# LMD18200.net
KiCad netlist of a schematic drawn in EAGLE
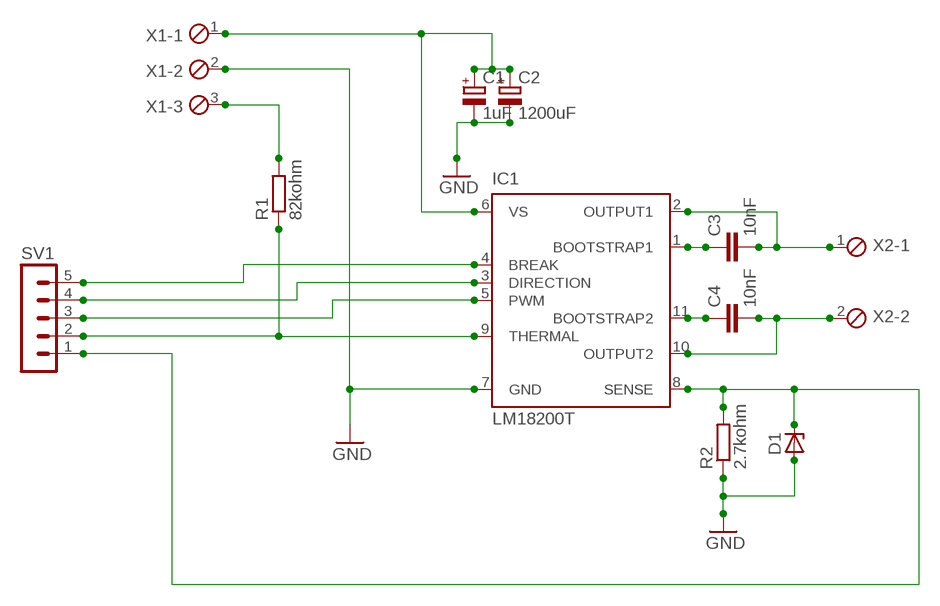
[diagram p0: schematic, sheet 1]

(export (version "E")
  (design (tool "Eeschema 10.0.6"))
  (components
    (comp (ref "C1")
      (value "1uF")
      (footprint "eagle-import:E2,5-6E")
      (libsource (lib "eagle-import") (part "CPOL-EUE2,5-6E"))
    )
    (comp (ref "C2")
      (value "1200uF")
      (footprint "eagle-import:E5-13")
      (libsource (lib "eagle-import") (part "CPOL-EUE5-13"))
    )
    (comp (ref "C3")
      (value "10nF")
      (footprint "eagle-import:C025-024X044")
      (libsource (lib "eagle-import") (part "C-EU025-024X044"))
    )
    (comp (ref "C4")
      (value "10nF")
      (footprint "eagle-import:C025-024X044")
      (libsource (lib "eagle-import") (part "C-EU025-024X044"))
    )
    (comp (ref "D1")
      (value "ZENER-DIODEZD-5")
      (footprint "eagle-import:ZDIO-5")
      (libsource (lib "eagle-import") (part "ZENER-DIODEZD-5"))
    )
    (comp (ref "IC1")
      (value "LM18200T")
      (footprint "eagle-import:TO-220-11")
      (libsource (lib "eagle-import") (part "LM18200T"))
    )
    (comp (ref "R1")
      (value "82kohm")
      (footprint "eagle-import:0204_5")
      (libsource (lib "eagle-import") (part "R-EU_0204/5"))
    )
    (comp (ref "R2")
      (value "2.7kohm")
      (footprint "eagle-import:0204_5")
      (libsource (lib "eagle-import") (part "R-EU_0204/5"))
    )
    (comp (ref "SV1")
      (value "MA05-1")
      (footprint "eagle-import:MA05-1")
      (libsource (lib "eagle-import") (part "MA05-1"))
    )
    (comp (ref "X1")
      (value "MPT3")
      (footprint "eagle-import:3POL254")
      (libsource (lib "eagle-import") (part "MPT3"))
    )
    (comp (ref "X2")
      (value "MPT2")
      (footprint "eagle-import:2POL254")
      (libsource (lib "eagle-import") (part "MPT2"))
    )
  )
  (nets
    (net (code "1") (name "GND") (class "Default")
      (node (ref "C1") (pin "-") (pinfunction "-_-") (pintype "passive"))
      (node (ref "C2") (pin "-") (pinfunction "-_-") (pintype "passive"))
      (node (ref "D1") (pin "A") (pinfunction "A_A") (pintype "passive"))
      (node (ref "IC1") (pin "7") (pinfunction "GND_7") (pintype "power_in"))
      (node (ref "R2") (pin "1") (pinfunction "1_1") (pintype "passive"))
      (node (ref "X1") (pin "2") (pinfunction "1_2") (pintype "passive"))
    )
    (net (code "2") (name "Net-(IC1-BOOTSTRAP1)") (class "Default")
      (node (ref "C3") (pin "1") (pinfunction "1_1") (pintype "passive"))
      (node (ref "IC1") (pin "1") (pinfunction "BOOTSTRAP1_1") (pintype "input"))
    )
    (net (code "3") (name "Net-(IC1-BOOTSTRAP2)") (class "Default")
      (node (ref "C4") (pin "1") (pinfunction "1_1") (pintype "passive"))
      (node (ref "IC1") (pin "11") (pinfunction "BOOTSTRAP2_11") (pintype "input"))
    )
    (net (code "4") (name "Net-(IC1-BREAK)") (class "Default")
      (node (ref "IC1") (pin "4") (pinfunction "BREAK_4") (pintype "input"))
      (node (ref "SV1") (pin "5") (pinfunction "5_5") (pintype "passive"))
    )
    (net (code "5") (name "Net-(IC1-DIRECTION)") (class "Default")
      (node (ref "IC1") (pin "3") (pinfunction "DIRECTION_3") (pintype "input"))
      (node (ref "SV1") (pin "4") (pinfunction "4_4") (pintype "passive"))
    )
    (net (code "6") (name "Net-(IC1-OUTPUT1)") (class "Default")
      (node (ref "C3") (pin "2") (pinfunction "2_2") (pintype "passive"))
      (node (ref "IC1") (pin "2") (pinfunction "OUTPUT1_2") (pintype "output"))
      (node (ref "X2") (pin "1") (pinfunction "1_1") (pintype "passive"))
    )
    (net (code "7") (name "Net-(IC1-OUTPUT2)") (class "Default")
      (node (ref "C4") (pin "2") (pinfunction "2_2") (pintype "passive"))
      (node (ref "IC1") (pin "10") (pinfunction "OUTPUT2_10") (pintype "output"))
      (node (ref "X2") (pin "2") (pinfunction "1_2") (pintype "passive"))
    )
    (net (code "8") (name "Net-(IC1-PWM)") (class "Default")
      (node (ref "IC1") (pin "5") (pinfunction "PWM_5") (pintype "input"))
      (node (ref "SV1") (pin "3") (pinfunction "3_3") (pintype "passive"))
    )
    (net (code "9") (name "Net-(IC1-SENSE)") (class "Default")
      (node (ref "D1") (pin "C") (pinfunction "C_C") (pintype "passive"))
      (node (ref "IC1") (pin "8") (pinfunction "SENSE_8") (pintype "output"))
      (node (ref "R2") (pin "2") (pinfunction "2_2") (pintype "passive"))
      (node (ref "SV1") (pin "1") (pinfunction "1_1") (pintype "passive"))
    )
    (net (code "10") (name "Net-(IC1-THERMAL)") (class "Default")
      (node (ref "IC1") (pin "9") (pinfunction "THERMAL_9") (pintype "output"))
      (node (ref "R1") (pin "1") (pinfunction "1_1") (pintype "passive"))
      (node (ref "SV1") (pin "2") (pinfunction "2_2") (pintype "passive"))
    )
    (net (code "11") (name "Net-(IC1-VS)") (class "Default")
      (node (ref "C1") (pin "+") (pinfunction "+_+") (pintype "passive"))
      (node (ref "C2") (pin "+") (pinfunction "+_+") (pintype "passive"))
      (node (ref "IC1") (pin "6") (pinfunction "VS_6") (pintype "power_in"))
      (node (ref "X1") (pin "1") (pinfunction "1_1") (pintype "passive"))
    )
    (net (code "12") (name "Net-(X1C-1)") (class "Default")
      (node (ref "R1") (pin "2") (pinfunction "2_2") (pintype "passive"))
      (node (ref "X1") (pin "3") (pinfunction "1_3") (pintype "passive"))
    )
  )
)
